# LR.net
KiCad netlist of a schematic drawn in Altium Designer
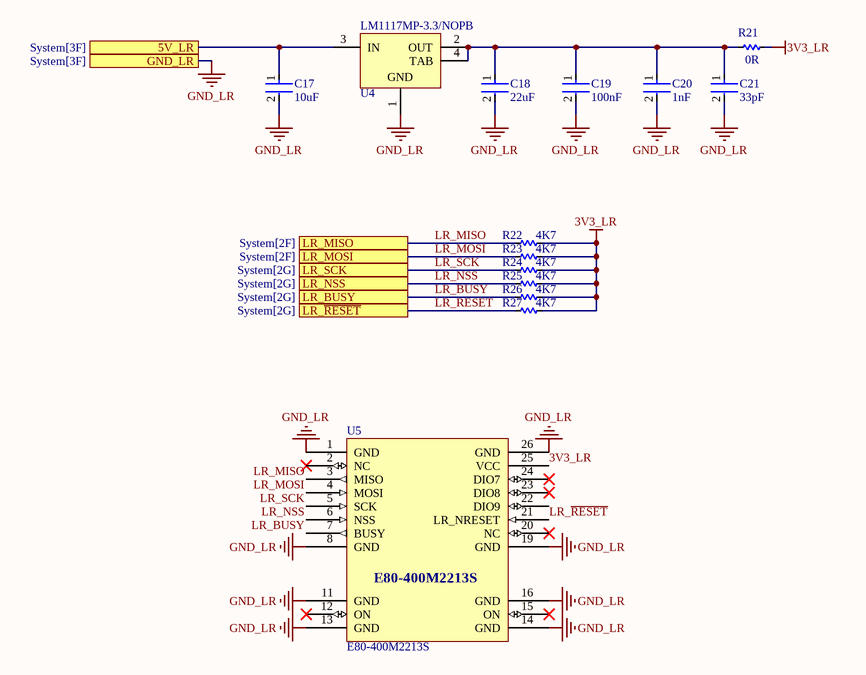
[diagram p0: LR.SchDoc]

(export (version "E")
  (design (tool "Eeschema 10.0.6"))
  (components
    (comp (ref "C17")
      (value "10uF")
      (footprint "FP-GRM188-0_1-e0_2_0_55-IPC_A")
      (description "Chip Multilayer Ceramic Capacitors for General Purpose, 0603")
      (fields (field (name "VOLTAGE") "6.3V") (field (name "TOLERANCE") "20%"))
      (libsource (lib "Altium Content Vault") (part "02cd4be3c70576c341d710602a673aa"))
    )
    (comp (ref "C18")
      (value "22uF")
      (footprint "FP-GRM188-0_1-e0_2_0_55-IPC_A")
      (description "Chip Multilayer Ceramic Capacitors for General Purpose, 0603")
      (fields (field (name "VOLTAGE") "6.3V") (field (name "TOLERANCE") "20%"))
      (libsource (lib "Altium Content Vault") (part "02cd4be3c70576c341d710602a673aa"))
    )
    (comp (ref "C19")
      (value "100nF")
      (footprint "FP-GRM188-0_1-e0_2_0_55-IPC_A")
      (description "Chip Multilayer Ceramic Capacitors for General Purpose, 0603")
      (fields (field (name "VOLTAGE") "6.3V") (field (name "TOLERANCE") "20%"))
      (libsource (lib "Altium Content Vault") (part "02cd4be3c70576c341d710602a673aa"))
    )
    (comp (ref "C20")
      (value "1nF")
      (footprint "FP-GRM188-0_1-e0_2_0_55-IPC_A")
      (description "Chip Multilayer Ceramic Capacitors for General Purpose, 0603")
      (fields (field (name "VOLTAGE") "6.3V") (field (name "TOLERANCE") "20%"))
      (libsource (lib "Altium Content Vault") (part "02cd4be3c70576c341d710602a673aa"))
    )
    (comp (ref "C21")
      (value "33pF")
      (footprint "FP-GRM188-0_1-e0_2_0_55-IPC_A")
      (description "Chip Multilayer Ceramic Capacitors for General Purpose, 0603")
      (fields (field (name "VOLTAGE") "6.3V") (field (name "TOLERANCE") "20%"))
      (libsource (lib "Altium Content Vault") (part "02cd4be3c70576c341d710602a673aa"))
    )
    (comp (ref "R21")
      (value "0R")
      (footprint "RES-SMD-0603")
      (description "Res 0603 5%")
      (fields
        (field (name "MANUFACTURER") "Generic Components")
        (field (name "PUBLISHER") "Altium Hobart Technology Centre")
      )
      (libsource (lib "TechMT.VN_Lib_Project v2") (part "Res-SMD"))
    )
    (comp (ref "R22")
      (value "4K7")
      (footprint "RES-SMD-0603")
      (description "Res 0603 5%")
      (fields
        (field (name "MANUFACTURER") "Generic Components")
        (field (name "PUBLISHER") "Altium Hobart Technology Centre")
      )
      (libsource (lib "TechMT.VN_Lib_Project v2") (part "Res-SMD"))
    )
    (comp (ref "R23")
      (value "4K7")
      (footprint "RES-SMD-0603")
      (description "Res 0603 5%")
      (fields
        (field (name "MANUFACTURER") "Generic Components")
        (field (name "PUBLISHER") "Altium Hobart Technology Centre")
      )
      (libsource (lib "TechMT.VN_Lib_Project v2") (part "Res-SMD"))
    )
    (comp (ref "R24")
      (value "4K7")
      (footprint "RES-SMD-0603")
      (description "Res 0603 5%")
      (fields
        (field (name "MANUFACTURER") "Generic Components")
        (field (name "PUBLISHER") "Altium Hobart Technology Centre")
      )
      (libsource (lib "TechMT.VN_Lib_Project v2") (part "Res-SMD"))
    )
    (comp (ref "R25")
      (value "4K7")
      (footprint "RES-SMD-0603")
      (description "Res 0603 5%")
      (fields
        (field (name "MANUFACTURER") "Generic Components")
        (field (name "PUBLISHER") "Altium Hobart Technology Centre")
      )
      (libsource (lib "TechMT.VN_Lib_Project v2") (part "Res-SMD"))
    )
    (comp (ref "R26")
      (value "4K7")
      (footprint "RES-SMD-0603")
      (description "Res 0603 5%")
      (fields
        (field (name "MANUFACTURER") "Generic Components")
        (field (name "PUBLISHER") "Altium Hobart Technology Centre")
      )
      (libsource (lib "TechMT.VN_Lib_Project v2") (part "Res-SMD"))
    )
    (comp (ref "R27")
      (value "4K7")
      (footprint "RES-SMD-0603")
      (description "Res 0603 5%")
      (fields
        (field (name "MANUFACTURER") "Generic Components")
        (field (name "PUBLISHER") "Altium Hobart Technology Centre")
      )
      (libsource (lib "TechMT.VN_Lib_Project v2") (part "Res-SMD"))
    )
    (comp (ref "U4")
      (value "LM1117MP-3.3/NOPB")
      (footprint "DCY0004A_M")
      (description "800mA Low-Dropout Linear Regulator, 4-pin SOT-223, Pb-Free")
      (fields (field (name "MANUFACTURER") "Texas Instruments"))
      (libsource (lib "Altium Content Vault") (part "PM-REG-LM1086-SOT4"))
    )
    (comp (ref "U5")
      (value "E80-400M2213S")
      (footprint "E80-400M2213S")
      (description "https://www.cdebyte.com/products/E80-400M2213S/2#Pin")
      (libsource (lib "atlab_altium_lib") (part "E80-400M2213S"))
    )
  )
  (nets
    (net (code "1") (name "/5V_LR") (class "Default")
      (node (ref "C17") (pin "1") (pinfunction "1_1") (pintype "passive"))
      (node (ref "U4") (pin "3") (pinfunction "IN_3") (pintype "power_in"))
    )
    (net (code "2") (name "/LR_BUSY") (class "Default")
      (node (ref "R26") (pin "1") (pinfunction "1_1") (pintype "passive"))
      (node (ref "U5") (pin "7") (pinfunction "BUSY_7") (pintype "output"))
    )
    (net (code "3") (name "/LR_MISO") (class "Default")
      (node (ref "R22") (pin "1") (pinfunction "1_1") (pintype "passive"))
      (node (ref "U5") (pin "3") (pinfunction "MISO_3") (pintype "output"))
    )
    (net (code "4") (name "/LR_MOSI") (class "Default")
      (node (ref "R23") (pin "1") (pinfunction "1_1") (pintype "passive"))
      (node (ref "U5") (pin "4") (pinfunction "MOSI_4") (pintype "input"))
    )
    (net (code "5") (name "/LR_NSS") (class "Default")
      (node (ref "R25") (pin "1") (pinfunction "1_1") (pintype "passive"))
      (node (ref "U5") (pin "6") (pinfunction "NSS_6") (pintype "input"))
    )
    (net (code "6") (name "/LR_SCK") (class "Default")
      (node (ref "R24") (pin "1") (pinfunction "1_1") (pintype "passive"))
      (node (ref "U5") (pin "5") (pinfunction "SCK_5") (pintype "input"))
    )
    (net (code "7") (name "/LR_~{RESET}") (class "Default")
      (node (ref "R27") (pin "1") (pinfunction "1_1") (pintype "passive"))
      (node (ref "U5") (pin "21") (pinfunction "LR_NRESET_21") (pintype "input"))
    )
    (net (code "8") (name "3V3_LR") (class "Default")
      (node (ref "R21") (pin "2") (pinfunction "2_2") (pintype "passive"))
      (node (ref "R22") (pin "2") (pinfunction "2_2") (pintype "passive"))
      (node (ref "R23") (pin "2") (pinfunction "2_2") (pintype "passive"))
      (node (ref "R24") (pin "2") (pinfunction "2_2") (pintype "passive"))
      (node (ref "R25") (pin "2") (pinfunction "2_2") (pintype "passive"))
      (node (ref "R26") (pin "2") (pinfunction "2_2") (pintype "passive"))
      (node (ref "R27") (pin "2") (pinfunction "2_2") (pintype "passive"))
      (node (ref "U5") (pin "25") (pinfunction "VCC_25") (pintype "power_in"))
    )
    (net (code "9") (name "GND_LR") (class "Default")
      (node (ref "C17") (pin "2") (pinfunction "2_2") (pintype "passive"))
      (node (ref "C18") (pin "2") (pinfunction "2_2") (pintype "passive"))
      (node (ref "C19") (pin "2") (pinfunction "2_2") (pintype "passive"))
      (node (ref "C20") (pin "2") (pinfunction "2_2") (pintype "passive"))
      (node (ref "C21") (pin "2") (pinfunction "2_2") (pintype "passive"))
      (node (ref "U4") (pin "1") (pinfunction "GND_1") (pintype "power_in"))
      (node (ref "U5") (pin "1") (pinfunction "GND_1") (pintype "power_in"))
      (node (ref "U5") (pin "11") (pinfunction "GND_11") (pintype "power_in"))
      (node (ref "U5") (pin "13") (pinfunction "GND_13") (pintype "power_in"))
      (node (ref "U5") (pin "14") (pinfunction "GND_14") (pintype "power_in"))
      (node (ref "U5") (pin "16") (pinfunction "GND_16") (pintype "power_in"))
      (node (ref "U5") (pin "19") (pinfunction "GND_19") (pintype "power_in"))
      (node (ref "U5") (pin "26") (pinfunction "GND_26") (pintype "power_in"))
      (node (ref "U5") (pin "8") (pinfunction "GND_8") (pintype "power_in"))
    )
    (net (code "10") (name "Net-(U4-OUT)") (class "Default")
      (node (ref "C18") (pin "1") (pinfunction "1_1") (pintype "passive"))
      (node (ref "C19") (pin "1") (pinfunction "1_1") (pintype "passive"))
      (node (ref "C20") (pin "1") (pinfunction "1_1") (pintype "passive"))
      (node (ref "C21") (pin "1") (pinfunction "1_1") (pintype "passive"))
      (node (ref "R21") (pin "1") (pinfunction "1_1") (pintype "passive"))
      (node (ref "U4") (pin "2") (pinfunction "OUT_2") (pintype "power_in"))
      (node (ref "U4") (pin "4") (pinfunction "TAB_4") (pintype "power_in"))
    )
    (net (code "11") (name "unconnected-(U5-DIO7-Pad24)") (class "Default")
      (node (ref "U5") (pin "24") (pinfunction "DIO7_24") (pintype "bidirectional+no_connect"))
    )
    (net (code "12") (name "unconnected-(U5-DIO8-Pad23)") (class "Default")
      (node (ref "U5") (pin "23") (pinfunction "DIO8_23") (pintype "bidirectional+no_connect"))
    )
    (net (code "13") (name "unconnected-(U5-DIO9-Pad22)") (class "Default")
      (node (ref "U5") (pin "22") (pinfunction "DIO9_22") (pintype "bidirectional"))
    )
    (net (code "14") (name "unconnected-(U5-NC-Pad2)") (class "Default")
      (node (ref "U5") (pin "2") (pinfunction "NC_2") (pintype "bidirectional+no_connect"))
    )
    (net (code "15") (name "unconnected-(U5-NC-Pad20)") (class "Default")
      (node (ref "U5") (pin "20") (pinfunction "NC_20") (pintype "bidirectional+no_connect"))
    )
    (net (code "16") (name "unconnected-(U5-ON-Pad12)") (class "Default")
      (node (ref "U5") (pin "12") (pinfunction "ON_12") (pintype "bidirectional+no_connect"))
    )
    (net (code "17") (name "unconnected-(U5-ON-Pad15)") (class "Default")
      (node (ref "U5") (pin "15") (pinfunction "ON_15") (pintype "bidirectional+no_connect"))
    )
  )
)
